# Power_board.net
KiCad netlist of a schematic drawn in Altium Designer
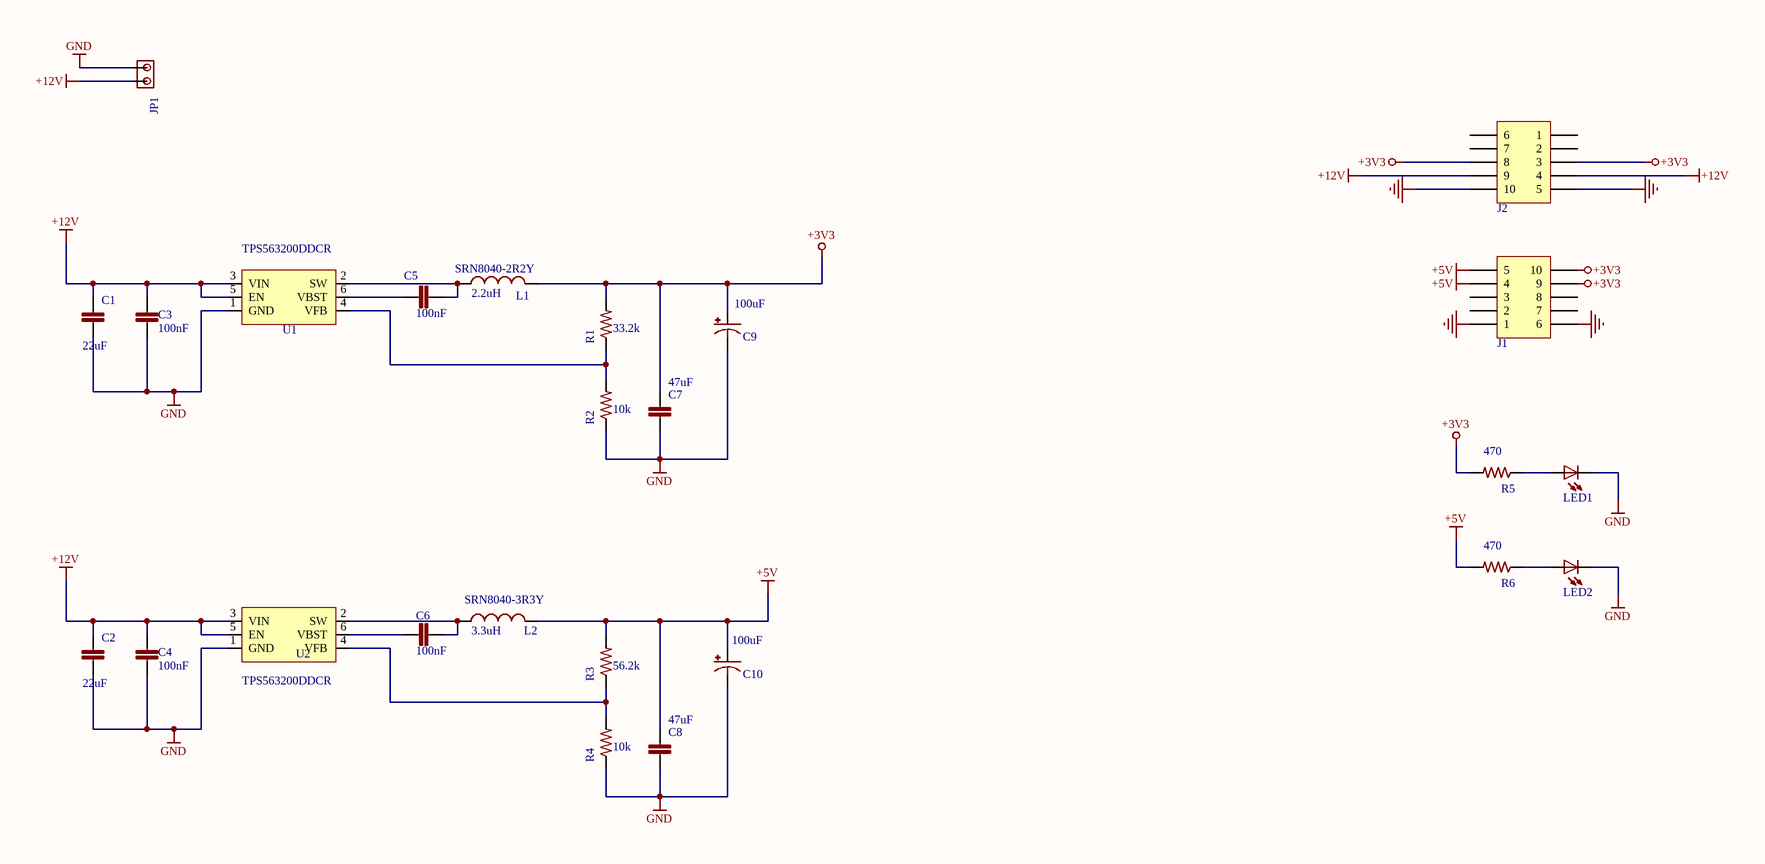
[diagram p0: Power_board.SchDoc]

(export (version "E")
  (design (tool "Eeschema 10.0.6"))
  (components
    (comp (ref "C1")
      (value "22uF")
      (footprint "C1206K")
      (description "CAPACITOR, European symbol")
      (fields (field (name "PART NUMBER") "GRM31CR61E226ME15K") (field (name "Comment") "Ceramic capacitor"))
      (libsource (lib "rcl") (part "C-EUC1206K"))
    )
    (comp (ref "C2")
      (value "22uF")
      (footprint "C1206K")
      (description "CAPACITOR, European symbol")
      (fields (field (name "PART NUMBER") "GRM31CR61E226ME15K") (field (name "Comment") "Ceramic capacitor"))
      (libsource (lib "rcl") (part "C-EUC1206K"))
    )
    (comp (ref "C3")
      (value "100nF")
      (footprint "C0603")
      (fields (field (name "PART NUMBER") "06033C104KAT2A") (field (name "Comment") "C-EUC0603"))
      (libsource (lib "") (part "C-EUC0603_1"))
    )
    (comp (ref "C4")
      (value "100nF")
      (footprint "C0603")
      (fields (field (name "PART NUMBER") "06033C104KAT2A") (field (name "Comment") "C-EUC0603"))
      (libsource (lib "") (part "C-EUC0603_1"))
    )
    (comp (ref "C5")
      (value "100nF")
      (footprint "C0603")
      (fields (field (name "PART NUMBER") "06033C104KAT2A") (field (name "Comment") "C-EUC0603"))
      (libsource (lib "rcl") (part "C-EUC0603"))
    )
    (comp (ref "C6")
      (value "100nF")
      (footprint "C0603")
      (fields (field (name "PART NUMBER") "06033C104KAT2A") (field (name "Comment") "C-EUC0603"))
      (libsource (lib "rcl") (part "C-EUC0603"))
    )
    (comp (ref "C7")
      (value "47uF")
      (footprint "C1206K")
      (description "CAPACITOR, European symbol")
      (fields (field (name "PART NUMBER") "GRM31CR61A476KE15L") (field (name "Comment") "Capacitor"))
      (libsource (lib "rcl") (part "C-EUC1206K"))
    )
    (comp (ref "C8")
      (value "47uF")
      (footprint "C1206K")
      (description "CAPACITOR, European symbol")
      (fields (field (name "PART NUMBER") "GRM31CR61A476KE15L") (field (name "Comment") "Capacitor"))
      (libsource (lib "rcl") (part "C-EUC1206K"))
    )
    (comp (ref "C9")
      (value "100uF")
      (footprint "153CLV-0505")
      (fields (field (name "PART NUMBER") "UWR1A101MCL1GB"))
      (libsource (lib "rcl") (part "CPOL-US153CLV-0505"))
    )
    (comp (ref "C10")
      (value "100uF")
      (footprint "153CLV-0505")
      (fields (field (name "PART NUMBER") "UWR1A101MCL1GB"))
      (libsource (lib "rcl") (part "CPOL-US153CLV-0505"))
    )
    (comp (ref "J1")
      (value "10p")
      (footprint "61301021121")
      (description "WR-PHD 2.54 mm THT Dual Pin Header, 10p")
      (fields (field (name "PART NUMBER") "61301021121"))
      (libsource (lib "Male_header_254mm") (part "61301021121"))
    )
    (comp (ref "J2")
      (value "10p")
      (footprint "61301021121")
      (description "WR-PHD 2.54 mm THT Dual Pin Header, 10p")
      (fields (field (name "PART NUMBER") "61301021121"))
      (libsource (lib "") (part "61301021121_1"))
    )
    (comp (ref "JP1")
      (value "CONECT_BAT")
      (footprint "CONECT_BAT_PCK")
      (libsource (lib "TE") (part "CONECT_BAT"))
    )
    (comp (ref "L1")
      (value "2.2uH")
      (footprint "SRN8040")
      (description "Imported")
      (fields (field (name "PART NUMBER") "SRN8040-2R2Y") (field (name "Comment") "SRN8040"))
      (libsource (lib "rcl") (part "L-US-SRN8040"))
    )
    (comp (ref "L2")
      (value "3.3uH")
      (footprint "SRN8040")
      (description "Imported")
      (fields (field (name "PART NUMBER") "SRN8040-3R3Y") (field (name "Comment") "SRN8040"))
      (libsource (lib "rcl") (part "L-US-SRN8040"))
    )
    (comp (ref "LED1")
      (value "LEDCHIPLED_0805")
      (footprint "CHIPLED_0805")
      (libsource (lib "led") (part "LEDCHIPLED_0805"))
    )
    (comp (ref "LED2")
      (value "LEDCHIPLED_0805")
      (footprint "CHIPLED_0805")
      (libsource (lib "led") (part "LEDCHIPLED_0805"))
    )
    (comp (ref "R1")
      (value "33.2k")
      (footprint "R0603")
      (description "RESISTOR, American symbol")
      (fields (field (name "PART NUMBER") "RR0816P-3322-D-51C"))
      (libsource (lib "rcl") (part "R-US_R0603"))
    )
    (comp (ref "R2")
      (value "10k")
      (footprint "R0603")
      (description "RESISTOR, American symbol")
      (fields (field (name "PART NUMBER") "RC0603FR-0710KL"))
      (libsource (lib "rcl") (part "R-US_R0603"))
    )
    (comp (ref "R3")
      (value "56.2k")
      (footprint "R0603")
      (description "RESISTOR, American symbol")
      (fields (field (name "PART NUMBER") "RR0816P-5622-D-73C"))
      (libsource (lib "rcl") (part "R-US_R0603"))
    )
    (comp (ref "R4")
      (value "10k")
      (footprint "R0603")
      (description "RESISTOR, American symbol")
      (fields (field (name "PART NUMBER") "RC0603FR-0710KL"))
      (libsource (lib "rcl") (part "R-US_R0603"))
    )
    (comp (ref "R5")
      (value "470")
      (footprint "R0603")
      (description "RESISTOR, American symbol")
      (fields (field (name "PART NUMBER") "ERJ-3GEYJ471V"))
      (libsource (lib "rcl") (part "R-US_R0603"))
    )
    (comp (ref "R6")
      (value "470")
      (footprint "R0603")
      (description "RESISTOR, American symbol")
      (fields (field (name "PART NUMBER") "ERJ-3GEYJ471V"))
      (libsource (lib "rcl") (part "R-US_R0603"))
    )
    (comp (ref "U1")
      (value "TPS563200")
      (footprint "DBV0006A_N")
      (fields (field (name "PART NUMBER") "TPS563200DDCR"))
      (libsource (lib "texas") (part "TPS563200"))
    )
    (comp (ref "U2")
      (value "TPS563200")
      (footprint "DBV0006A_N")
      (fields (field (name "PART NUMBER") "TPS563200DDCR"))
      (libsource (lib "texas") (part "TPS563200"))
    )
  )
  (nets
    (net (code "1") (name "+3V3") (class "Default")
      (node (ref "C7") (pin "1") (pinfunction "1_1") (pintype "passive"))
      (node (ref "C9") (pin "+") (pinfunction "+_+") (pintype "passive"))
      (node (ref "J1") (pin "10") (pinfunction "10_10") (pintype "passive"))
      (node (ref "J1") (pin "9") (pinfunction "9_9") (pintype "passive"))
      (node (ref "J2") (pin "3") (pinfunction "3_3") (pintype "passive"))
      (node (ref "J2") (pin "8") (pinfunction "8_8") (pintype "passive"))
      (node (ref "L1") (pin "2") (pinfunction "2_2") (pintype "passive"))
      (node (ref "R1") (pin "2") (pinfunction "2_2") (pintype "passive"))
      (node (ref "R5") (pin "2") (pinfunction "2_2") (pintype "passive"))
    )
    (net (code "2") (name "+5V") (class "Default")
      (node (ref "C10") (pin "+") (pinfunction "+_+") (pintype "passive"))
      (node (ref "C8") (pin "1") (pinfunction "1_1") (pintype "passive"))
      (node (ref "J1") (pin "4") (pinfunction "4_4") (pintype "passive"))
      (node (ref "J1") (pin "5") (pinfunction "5_5") (pintype "passive"))
      (node (ref "L2") (pin "2") (pinfunction "2_2") (pintype "passive"))
      (node (ref "R3") (pin "2") (pinfunction "2_2") (pintype "passive"))
      (node (ref "R6") (pin "2") (pinfunction "2_2") (pintype "passive"))
    )
    (net (code "3") (name "+12V") (class "Default")
      (node (ref "C1") (pin "1") (pinfunction "1_1") (pintype "passive"))
      (node (ref "C2") (pin "1") (pinfunction "1_1") (pintype "passive"))
      (node (ref "C3") (pin "1") (pinfunction "1_1") (pintype "passive"))
      (node (ref "C4") (pin "1") (pinfunction "1_1") (pintype "passive"))
      (node (ref "J2") (pin "4") (pinfunction "4_4") (pintype "passive"))
      (node (ref "J2") (pin "9") (pinfunction "9_9") (pintype "passive"))
      (node (ref "JP1") (pin "2") (pinfunction "2_2") (pintype "passive"))
      (node (ref "U1") (pin "3") (pinfunction "VIN_3") (pintype "passive"))
      (node (ref "U1") (pin "5") (pinfunction "EN_5") (pintype "passive"))
      (node (ref "U2") (pin "3") (pinfunction "VIN_3") (pintype "passive"))
      (node (ref "U2") (pin "5") (pinfunction "EN_5") (pintype "passive"))
    )
    (net (code "4") (name "GND") (class "Default")
      (node (ref "C1") (pin "2") (pinfunction "2_2") (pintype "passive"))
      (node (ref "C10") (pin "-") (pinfunction "-_-") (pintype "passive"))
      (node (ref "C2") (pin "2") (pinfunction "2_2") (pintype "passive"))
      (node (ref "C3") (pin "2") (pinfunction "2_2") (pintype "passive"))
      (node (ref "C4") (pin "2") (pinfunction "2_2") (pintype "passive"))
      (node (ref "C7") (pin "2") (pinfunction "2_2") (pintype "passive"))
      (node (ref "C8") (pin "2") (pinfunction "2_2") (pintype "passive"))
      (node (ref "C9") (pin "-") (pinfunction "-_-") (pintype "passive"))
      (node (ref "J1") (pin "1") (pinfunction "1_1") (pintype "passive"))
      (node (ref "J1") (pin "6") (pinfunction "6_6") (pintype "passive"))
      (node (ref "J2") (pin "10") (pinfunction "10_10") (pintype "passive"))
      (node (ref "J2") (pin "5") (pinfunction "5_5") (pintype "passive"))
      (node (ref "JP1") (pin "1") (pinfunction "1_1") (pintype "passive"))
      (node (ref "LED1") (pin "C") (pinfunction "C_C") (pintype "passive"))
      (node (ref "LED2") (pin "C") (pinfunction "C_C") (pintype "passive"))
      (node (ref "R2") (pin "1") (pinfunction "1_1") (pintype "passive"))
      (node (ref "R4") (pin "1") (pinfunction "1_1") (pintype "passive"))
      (node (ref "U1") (pin "1") (pinfunction "GND_1") (pintype "power_in"))
      (node (ref "U2") (pin "1") (pinfunction "GND_1") (pintype "power_in"))
    )
    (net (code "5") (name "Net-(LED1-PadA)") (class "Default")
      (node (ref "LED1") (pin "A") (pinfunction "A_A") (pintype "passive"))
      (node (ref "R5") (pin "1") (pinfunction "1_1") (pintype "passive"))
    )
    (net (code "6") (name "Net-(LED2-PadA)") (class "Default")
      (node (ref "LED2") (pin "A") (pinfunction "A_A") (pintype "passive"))
      (node (ref "R6") (pin "1") (pinfunction "1_1") (pintype "passive"))
    )
    (net (code "7") (name "Net-(U1-SW)") (class "Default")
      (node (ref "C5") (pin "2") (pinfunction "2_2") (pintype "passive"))
      (node (ref "L1") (pin "1") (pinfunction "1_1") (pintype "passive"))
      (node (ref "U1") (pin "2") (pinfunction "SW_2") (pintype "passive"))
    )
    (net (code "8") (name "Net-(U1-VBST)") (class "Default")
      (node (ref "C5") (pin "1") (pinfunction "1_1") (pintype "passive"))
      (node (ref "U1") (pin "6") (pinfunction "VBST_6") (pintype "passive"))
    )
    (net (code "9") (name "Net-(U1-VFB)") (class "Default")
      (node (ref "R1") (pin "1") (pinfunction "1_1") (pintype "passive"))
      (node (ref "R2") (pin "2") (pinfunction "2_2") (pintype "passive"))
      (node (ref "U1") (pin "4") (pinfunction "VFB_4") (pintype "passive"))
    )
    (net (code "10") (name "Net-(U2-SW)") (class "Default")
      (node (ref "C6") (pin "2") (pinfunction "2_2") (pintype "passive"))
      (node (ref "L2") (pin "1") (pinfunction "1_1") (pintype "passive"))
      (node (ref "U2") (pin "2") (pinfunction "SW_2") (pintype "passive"))
    )
    (net (code "11") (name "Net-(U2-VBST)") (class "Default")
      (node (ref "C6") (pin "1") (pinfunction "1_1") (pintype "passive"))
      (node (ref "U2") (pin "6") (pinfunction "VBST_6") (pintype "passive"))
    )
    (net (code "12") (name "Net-(U2-VFB)") (class "Default")
      (node (ref "R3") (pin "1") (pinfunction "1_1") (pintype "passive"))
      (node (ref "R4") (pin "2") (pinfunction "2_2") (pintype "passive"))
      (node (ref "U2") (pin "4") (pinfunction "VFB_4") (pintype "passive"))
    )
    (net (code "13") (name "unconnected-(J1-Pad2)") (class "Default")
      (node (ref "J1") (pin "2") (pinfunction "2_2") (pintype "passive"))
    )
    (net (code "14") (name "unconnected-(J1-Pad3)") (class "Default")
      (node (ref "J1") (pin "3") (pinfunction "3_3") (pintype "passive"))
    )
    (net (code "15") (name "unconnected-(J1-Pad7)") (class "Default")
      (node (ref "J1") (pin "7") (pinfunction "7_7") (pintype "passive"))
    )
    (net (code "16") (name "unconnected-(J1-Pad8)") (class "Default")
      (node (ref "J1") (pin "8") (pinfunction "8_8") (pintype "passive"))
    )
    (net (code "17") (name "unconnected-(J2-Pad1)") (class "Default")
      (node (ref "J2") (pin "1") (pinfunction "1_1") (pintype "passive"))
    )
    (net (code "18") (name "unconnected-(J2-Pad2)") (class "Default")
      (node (ref "J2") (pin "2") (pinfunction "2_2") (pintype "passive"))
    )
    (net (code "19") (name "unconnected-(J2-Pad6)") (class "Default")
      (node (ref "J2") (pin "6") (pinfunction "6_6") (pintype "passive"))
    )
    (net (code "20") (name "unconnected-(J2-Pad7)") (class "Default")
      (node (ref "J2") (pin "7") (pinfunction "7_7") (pintype "passive"))
    )
  )
)
